# Flight_Controller.net
KiCad netlist of a schematic drawn in Altium Designer
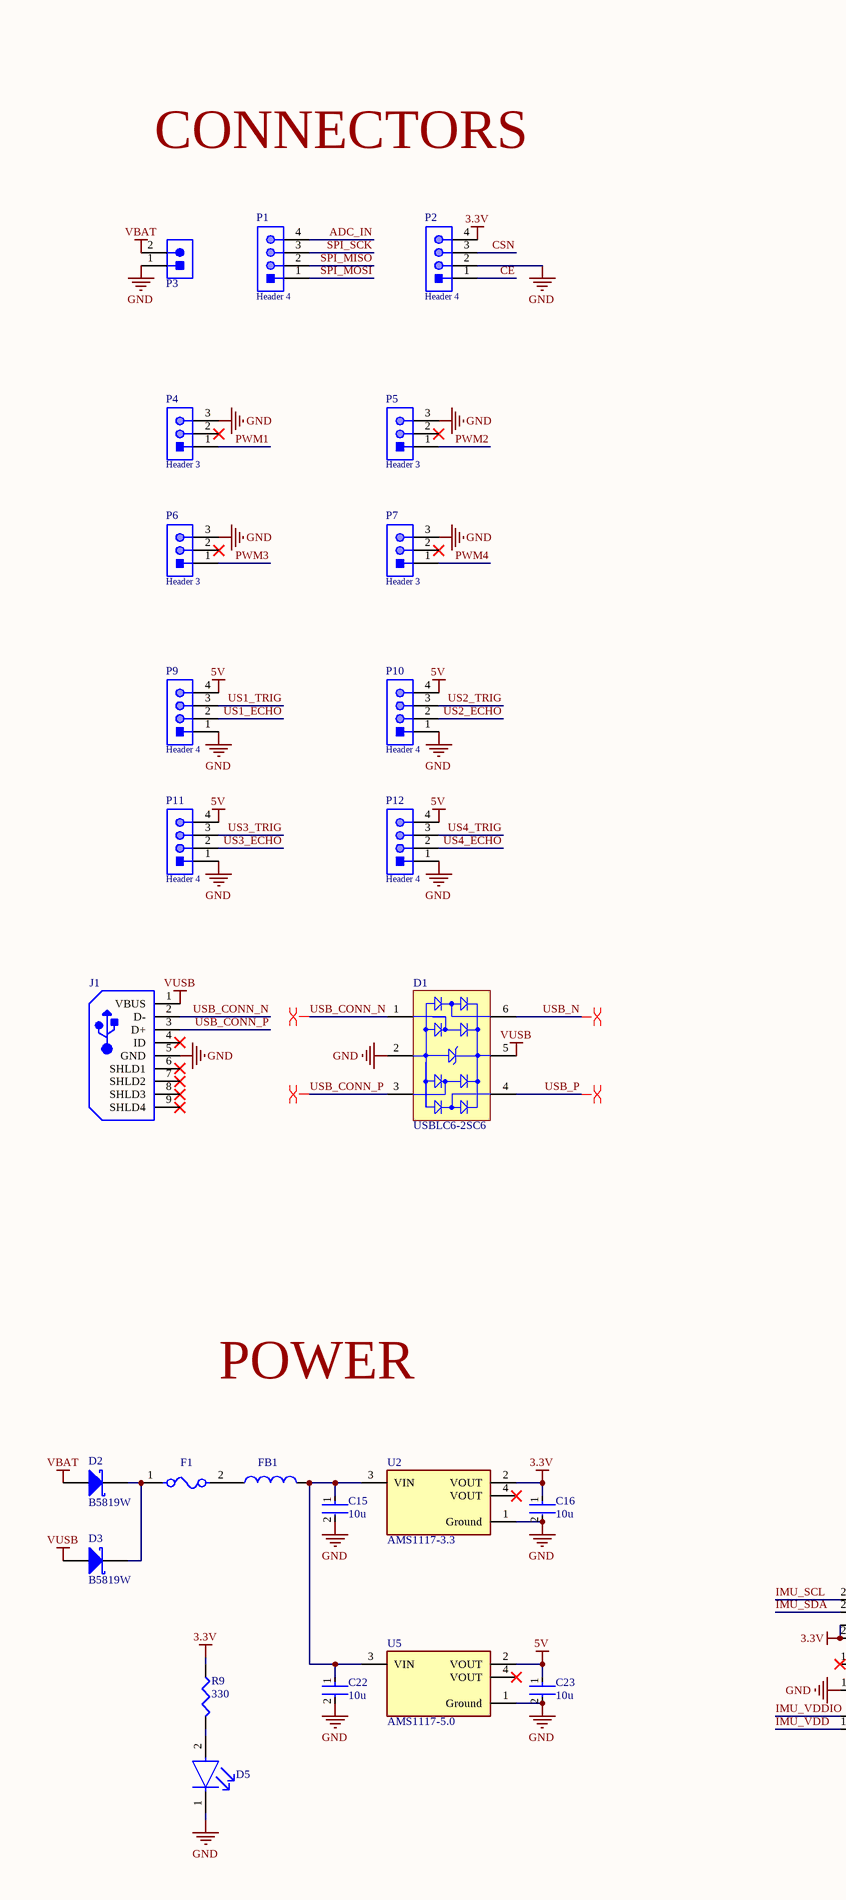
[diagram p0: Flight Controller.SchDoc, left]
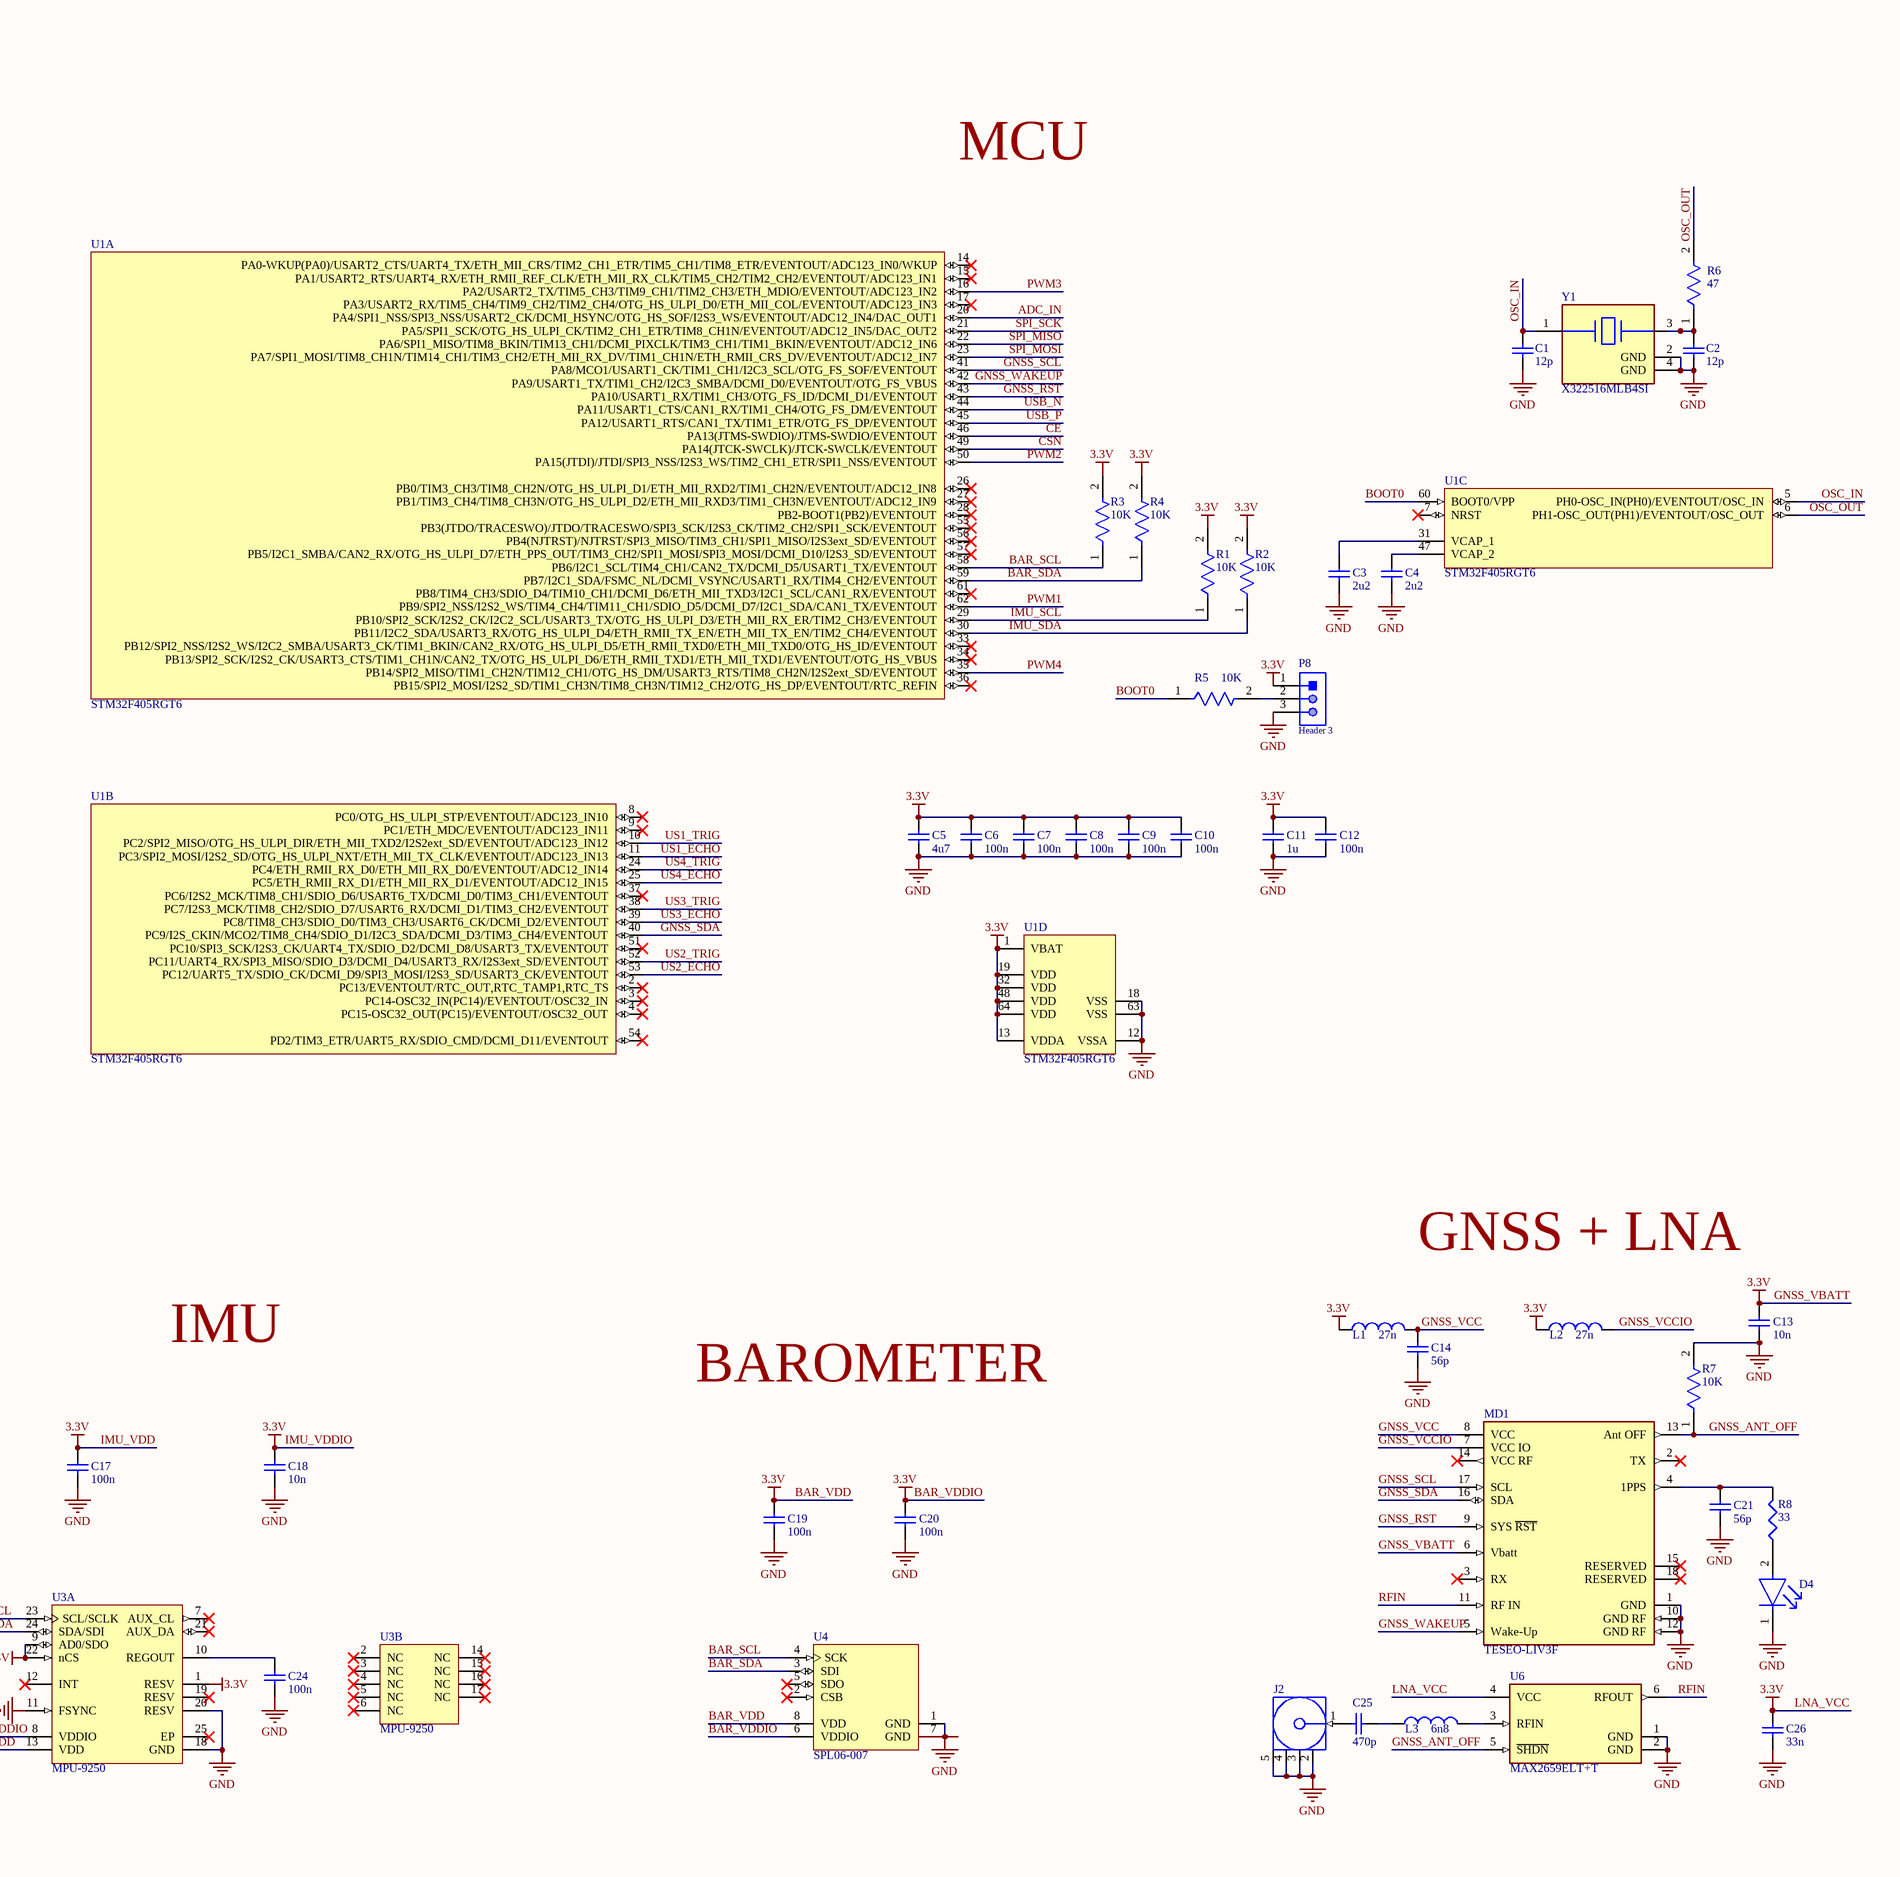
[diagram p1: Flight Controller.SchDoc, right]

(export (version "E")
  (design (tool "Eeschema 10.0.6"))
  (components
    (comp (ref "C1")
      (value "12p")
      (footprint "0402")
      (description "Capacitor (Semiconductor SIM Model)")
      (fields (field (name "Comment") "Cap Semi") (field (name "PUBLISHER") "Altium Limited"))
      (libsource (lib "Miscellaneous Devices") (part "Cap Semi"))
    )
    (comp (ref "C2")
      (value "12p")
      (footprint "0402")
      (description "Capacitor (Semiconductor SIM Model)")
      (fields (field (name "Comment") "Cap Semi") (field (name "PUBLISHER") "Altium Limited"))
      (libsource (lib "Miscellaneous Devices") (part "Cap Semi"))
    )
    (comp (ref "C3")
      (value "2u2")
      (footprint "1608[0603]")
      (description "Capacitor (Semiconductor SIM Model)")
      (fields (field (name "Comment") "Cap Semi") (field (name "PUBLISHER") "Altium Limited"))
      (libsource (lib "Miscellaneous Devices") (part "Cap Semi"))
    )
    (comp (ref "C4")
      (value "2u2")
      (footprint "1608[0603]")
      (description "Capacitor (Semiconductor SIM Model)")
      (fields (field (name "Comment") "Cap Semi") (field (name "PUBLISHER") "Altium Limited"))
      (libsource (lib "Miscellaneous Devices") (part "Cap Semi"))
    )
    (comp (ref "C5")
      (value "4u7")
      (footprint "1608[0603]")
      (description "Capacitor (Semiconductor SIM Model)")
      (fields (field (name "Comment") "Cap Semi") (field (name "PUBLISHER") "Altium Limited"))
      (libsource (lib "Miscellaneous Devices") (part "Cap Semi"))
    )
    (comp (ref "C6")
      (value "100n")
      (footprint "0402")
      (description "Capacitor (Semiconductor SIM Model)")
      (fields (field (name "Comment") "Cap Semi") (field (name "PUBLISHER") "Altium Limited"))
      (libsource (lib "Miscellaneous Devices") (part "Cap Semi"))
    )
    (comp (ref "C7")
      (value "100n")
      (footprint "0402")
      (description "Capacitor (Semiconductor SIM Model)")
      (fields (field (name "Comment") "Cap Semi") (field (name "PUBLISHER") "Altium Limited"))
      (libsource (lib "Miscellaneous Devices") (part "Cap Semi"))
    )
    (comp (ref "C8")
      (value "100n")
      (footprint "0402")
      (description "Capacitor (Semiconductor SIM Model)")
      (fields (field (name "Comment") "Cap Semi") (field (name "PUBLISHER") "Altium Limited"))
      (libsource (lib "Miscellaneous Devices") (part "Cap Semi"))
    )
    (comp (ref "C9")
      (value "100n")
      (footprint "0402")
      (description "Capacitor (Semiconductor SIM Model)")
      (fields (field (name "Comment") "Cap Semi") (field (name "PUBLISHER") "Altium Limited"))
      (libsource (lib "Miscellaneous Devices") (part "Cap Semi"))
    )
    (comp (ref "C10")
      (value "100n")
      (footprint "0402")
      (description "Capacitor (Semiconductor SIM Model)")
      (fields (field (name "Comment") "Cap Semi") (field (name "PUBLISHER") "Altium Limited"))
      (libsource (lib "Miscellaneous Devices") (part "Cap Semi"))
    )
    (comp (ref "C11")
      (value "1u")
      (footprint "1608[0603]")
      (description "Capacitor (Semiconductor SIM Model)")
      (fields (field (name "Comment") "Cap Semi") (field (name "PUBLISHER") "Altium Limited"))
      (libsource (lib "Miscellaneous Devices") (part "Cap Semi"))
    )
    (comp (ref "C12")
      (value "100n")
      (footprint "0402")
      (description "Capacitor (Semiconductor SIM Model)")
      (fields (field (name "Comment") "Cap Semi") (field (name "PUBLISHER") "Altium Limited"))
      (libsource (lib "Miscellaneous Devices") (part "Cap Semi"))
    )
    (comp (ref "C13")
      (value "10n")
      (footprint "0402")
      (description "Capacitor (Semiconductor SIM Model)")
      (fields (field (name "Comment") "Cap Semi") (field (name "PUBLISHER") "Altium Limited"))
      (libsource (lib "Miscellaneous Devices") (part "Cap Semi"))
    )
    (comp (ref "C14")
      (value "56p")
      (footprint "0402")
      (description "Capacitor (Semiconductor SIM Model)")
      (fields (field (name "Comment") "Cap Semi") (field (name "PUBLISHER") "Altium Limited"))
      (libsource (lib "Miscellaneous Devices") (part "Cap Semi"))
    )
    (comp (ref "C15")
      (value "10u")
      (footprint "FP-CL21-IPC_B")
      (description "CL21 Series 0805 10uF 25V ±10% Tolerance X5R Multilayer Ceramic Chip Capacitor")
      (fields (field (name "TOLERANCE") "10%"))
      (libsource (lib "Altium Content Vault") (part "b4654b650e69147ec39a6b967a45e02"))
    )
    (comp (ref "C16")
      (value "10u")
      (footprint "FP-CL21-IPC_B")
      (description "CL21 Series 0805 10uF 25V ±10% Tolerance X5R Multilayer Ceramic Chip Capacitor")
      (fields (field (name "TOLERANCE") "10%"))
      (libsource (lib "Altium Content Vault") (part "b4654b650e69147ec39a6b967a45e02"))
    )
    (comp (ref "C17")
      (value "100n")
      (footprint "0402")
      (description "Capacitor (Semiconductor SIM Model)")
      (fields (field (name "Comment") "Cap Semi") (field (name "PUBLISHER") "Altium Limited"))
      (libsource (lib "Miscellaneous Devices") (part "Cap Semi"))
    )
    (comp (ref "C18")
      (value "10n")
      (footprint "0402")
      (description "Capacitor (Semiconductor SIM Model)")
      (fields (field (name "Comment") "Cap Semi") (field (name "PUBLISHER") "Altium Limited"))
      (libsource (lib "Miscellaneous Devices") (part "Cap Semi"))
    )
    (comp (ref "C19")
      (value "100n")
      (footprint "0402")
      (description "Capacitor (Semiconductor SIM Model)")
      (fields (field (name "Comment") "Cap Semi") (field (name "PUBLISHER") "Altium Limited"))
      (libsource (lib "Miscellaneous Devices") (part "Cap Semi"))
    )
    (comp (ref "C20")
      (value "100n")
      (footprint "0402")
      (description "Capacitor (Semiconductor SIM Model)")
      (fields (field (name "Comment") "Cap Semi") (field (name "PUBLISHER") "Altium Limited"))
      (libsource (lib "Miscellaneous Devices") (part "Cap Semi"))
    )
    (comp (ref "C21")
      (value "56p")
      (footprint "0402")
      (description "Capacitor (Semiconductor SIM Model)")
      (fields (field (name "Comment") "Cap Semi") (field (name "PUBLISHER") "Altium Limited"))
      (libsource (lib "Miscellaneous Devices") (part "Cap Semi"))
    )
    (comp (ref "C22")
      (value "10u")
      (footprint "FP-CL21-IPC_B")
      (description "CL21 Series 0805 10uF 25V ±10% Tolerance X5R Multilayer Ceramic Chip Capacitor")
      (fields (field (name "TOLERANCE") "10%"))
      (libsource (lib "Altium Content Vault") (part "b4654b650e69147ec39a6b967a45e02"))
    )
    (comp (ref "C23")
      (value "10u")
      (footprint "FP-CL21-IPC_B")
      (description "CL21 Series 0805 10uF 25V ±10% Tolerance X5R Multilayer Ceramic Chip Capacitor")
      (fields (field (name "TOLERANCE") "10%"))
      (libsource (lib "Altium Content Vault") (part "b4654b650e69147ec39a6b967a45e02"))
    )
    (comp (ref "C24")
      (value "100n")
      (footprint "0402")
      (description "Capacitor (Semiconductor SIM Model)")
      (fields (field (name "Comment") "Cap Semi") (field (name "PUBLISHER") "Altium Limited"))
      (libsource (lib "Miscellaneous Devices") (part "Cap Semi"))
    )
    (comp (ref "C25")
      (value "470p")
      (footprint "0402")
      (description "Capacitor (Semiconductor SIM Model)")
      (fields (field (name "Comment") "Cap Semi") (field (name "PUBLISHER") "Altium Limited"))
      (libsource (lib "Miscellaneous Devices") (part "Cap Semi"))
    )
    (comp (ref "C26")
      (value "33n")
      (footprint "0402")
      (description "Capacitor (Semiconductor SIM Model)")
      (fields (field (name "Comment") "Cap Semi") (field (name "PUBLISHER") "Altium Limited"))
      (libsource (lib "Miscellaneous Devices") (part "Cap Semi"))
    )
    (comp (ref "D1")
      (value "USBLC6-2SC6")
      (footprint "STM-SOT23-6L_V")
      (description "Very low capacitance ESD protection, 3.5 pF, -40 to 125 degC, 6-Pin SOT23, RoHS, Tape and Reel")
      (fields (field (name "MANUFACTURER") "STMicroelectronics"))
      (libsource (lib "Altium Content Vault") (part "STM-USB_DVI_HDMIULC6-4SC6X-SOT23-6L"))
    )
    (comp (ref "D2")
      (value "B5819W")
      (footprint "MCC-SOD123_V")
      (description "Schottky Barrier Rectifier, 1 A, 40 Vrm, -65 to 125 degC, 2-Pin SOD123, RoHS, Tape and Reel")
      (fields (field (name "MANUFACTURER") "Micro Commercial Components"))
      (libsource (lib "Altium Content Vault") (part "DSKY-AK-2"))
    )
    (comp (ref "D3")
      (value "B5819W")
      (footprint "MCC-SOD123_V")
      (description "Schottky Barrier Rectifier, 1 A, 40 Vrm, -65 to 125 degC, 2-Pin SOD123, RoHS, Tape and Reel")
      (fields (field (name "MANUFACTURER") "Micro Commercial Components"))
      (libsource (lib "Altium Content Vault") (part "DSKY-AK-2"))
    )
    (comp (ref "D4")
      (value "597-3901-831F")
      (footprint "FP-597-MFG")
      (description "LED COOL WHITE 2SMD")
      (fields
        (field (name "OCTOPART") "https://octopart.com/597-3901-831f-dialight-10598902")
        (field (name "MANUFACTURER") "Dialight")
      )
      (libsource (lib "Altium Content Vault") (part "8706943c75ba83719d021d2fdc84c58"))
    )
    (comp (ref "D5")
      (value "597-3901-831F")
      (footprint "FP-597-MFG")
      (description "LED COOL WHITE 2SMD")
      (fields
        (field (name "OCTOPART") "https://octopart.com/597-3901-831f-dialight-10598902")
        (field (name "MANUFACTURER") "Dialight")
      )
      (libsource (lib "Altium Content Vault") (part "8706943c75ba83719d021d2fdc84c58"))
    )
    (comp (ref "F1")
      (value "nSMD050-24V")
      (footprint "FP-0466-MFG")
      (description "FUSE BOARD MNT 1A 63VAC/VDC 1206")
      (fields
        (field (name "MANUFACTURER PART NUMBER") "0466001.NR")
        (field (name "MANUFACTURER") "Littelfuse Inc")
      )
      (libsource (lib "Altium Content Vault") (part "5bcf9b9f640e542cf0359d10258e979"))
    )
    (comp (ref "FB1")
      (value "GZ2012D601TF")
      (footprint "SNLD-CHIP2-2012X105_V")
      (fields (field (name "MANUFACTURER") "Sunlord"))
      (libsource (lib "Altium Content Vault") (part "SNLD-FB-2"))
    )
    (comp (ref "J1")
      (value "65100516121")
      (footprint "WE-65100516121_V")
      (description "MINI USB 2.0 SMT Type B 5 Contacts, 30 V, -40 to 105 degC, RoHS, Tape and Reel")
      (fields (field (name "MANUFACTURER") "Wuerth Elektronik"))
      (libsource (lib "Altium Content Vault") (part "USB-5-4SHLD"))
    )
    (comp (ref "J2")
      (value "CONSMA001")
      (footprint "CON-SMA")
      (description "Female PCB Mount Connector, Thru-Hole")
      (libsource (lib "Altium Content Vault") (part "CN-1P-F-RF5"))
    )
    (comp (ref "L1")
      (value "27n")
      (footprint "0402-A")
      (description "Inductor")
      (fields (field (name "PUBLISHER") "Altium Limited"))
      (libsource (lib "Miscellaneous Devices") (part "Inductor"))
    )
    (comp (ref "L2")
      (value "27n")
      (footprint "0402-A")
      (description "Inductor")
      (fields (field (name "PUBLISHER") "Altium Limited"))
      (libsource (lib "Miscellaneous Devices") (part "Inductor"))
    )
    (comp (ref "L3")
      (value "6n8")
      (footprint "0402-A")
      (description "Inductor")
      (fields (field (name "PUBLISHER") "Altium Limited"))
      (libsource (lib "Miscellaneous Devices") (part "Inductor"))
    )
    (comp (ref "MD1")
      (value "TESEO-LIV3F")
      (footprint "FP-LCC-18-MFG")
      (description "RF RCVR GNSS/GPS 1.575GHZ 18LCC")
      (fields
        (field (name "MANUFACTURER") "STMicroelectronics")
        (field (name "OCTOPART") "https://octopart.com/teseo-liv3f-stmicroelectronics-84762432")
      )
      (libsource (lib "Altium Content Vault") (part "a9d99e4f4ab5d9a165d150092334cf6"))
    )
    (comp (ref "P1")
      (value "Header 4")
      (footprint "61300411121")
      (description "THT Vertical Pin Header WR-PHD, Pitch 2.54 mm, Single Row, 4 pins")
      (fields
        (field (name "MANUFACTURER") "Wurth Elektronik")
        (field (name "PART NUMBER") "61300411121")
        (field (name "PUBLISHER") "WurthElektronik")
      )
      (libsource (lib "Altium Content Vault") (part "WE-CN-1P-M-R4"))
    )
    (comp (ref "P2")
      (value "Header 4")
      (footprint "61300411121")
      (description "THT Vertical Pin Header WR-PHD, Pitch 2.54 mm, Single Row, 4 pins")
      (fields
        (field (name "MANUFACTURER") "Wurth Elektronik")
        (field (name "PART NUMBER") "61300411121")
        (field (name "PUBLISHER") "WurthElektronik")
      )
      (libsource (lib "Altium Content Vault") (part "WE-CN-1P-M-R4"))
    )
    (comp (ref "P3")
      (value "SCREW-5.0/5.08 2WAYS")
      (footprint "SCREW-5.0-2WAYS_V")
      (description "Socket, Screw Terminal Block, 2 Way, 5.0 mm Pitch, 90 Degree Angle, Through-Hole")
      (fields (field (name "MANUFACTURER") "No Vendor"))
      (libsource (lib "Altium Content Vault") (part "SCREW-2WAYS"))
    )
    (comp (ref "P4")
      (value "Header 3")
      (footprint "61300311121")
      (description "THT Vertical Pin Header WR-PHD, Pitch 2.54 mm, Single Row, 3 pins")
      (fields
        (field (name "PART NUMBER") "61300311121")
        (field (name "MANUFACTURER") "Wurth Elektronik")
        (field (name "PUBLISHER") "WurthElektronik")
      )
      (libsource (lib "Altium Content Vault") (part "WE-CN-1P-M-R3"))
    )
    (comp (ref "P5")
      (value "Header 3")
      (footprint "61300311121")
      (description "THT Vertical Pin Header WR-PHD, Pitch 2.54 mm, Single Row, 3 pins")
      (fields
        (field (name "PART NUMBER") "61300311121")
        (field (name "MANUFACTURER") "Wurth Elektronik")
        (field (name "PUBLISHER") "WurthElektronik")
      )
      (libsource (lib "Altium Content Vault") (part "WE-CN-1P-M-R3"))
    )
    (comp (ref "P6")
      (value "Header 3")
      (footprint "61300311121")
      (description "THT Vertical Pin Header WR-PHD, Pitch 2.54 mm, Single Row, 3 pins")
      (fields
        (field (name "PART NUMBER") "61300311121")
        (field (name "MANUFACTURER") "Wurth Elektronik")
        (field (name "PUBLISHER") "WurthElektronik")
      )
      (libsource (lib "Altium Content Vault") (part "WE-CN-1P-M-R3"))
    )
    (comp (ref "P7")
      (value "Header 3")
      (footprint "61300311121")
      (description "THT Vertical Pin Header WR-PHD, Pitch 2.54 mm, Single Row, 3 pins")
      (fields
        (field (name "PART NUMBER") "61300311121")
        (field (name "MANUFACTURER") "Wurth Elektronik")
        (field (name "PUBLISHER") "WurthElektronik")
      )
      (libsource (lib "Altium Content Vault") (part "WE-CN-1P-M-R3"))
    )
    (comp (ref "P8")
      (value "Header 3")
      (footprint "61300311121")
      (description "THT Vertical Pin Header WR-PHD, Pitch 2.54 mm, Single Row, 3 pins")
      (fields
        (field (name "PART NUMBER") "61300311121")
        (field (name "MANUFACTURER") "Wurth Elektronik")
        (field (name "PUBLISHER") "WurthElektronik")
      )
      (libsource (lib "") (part "WE-CN-1P-M-R3_1"))
    )
    (comp (ref "P9")
      (value "Header 4")
      (footprint "61300411121")
      (description "THT Vertical Pin Header WR-PHD, Pitch 2.54 mm, Single Row, 4 pins")
      (fields
        (field (name "MANUFACTURER") "Wurth Elektronik")
        (field (name "PART NUMBER") "61300411121")
        (field (name "PUBLISHER") "WurthElektronik")
      )
      (libsource (lib "Altium Content Vault") (part "WE-CN-1P-M-R4"))
    )
    (comp (ref "P10")
      (value "Header 4")
      (footprint "61300411121")
      (description "THT Vertical Pin Header WR-PHD, Pitch 2.54 mm, Single Row, 4 pins")
      (fields
        (field (name "MANUFACTURER") "Wurth Elektronik")
        (field (name "PART NUMBER") "61300411121")
        (field (name "PUBLISHER") "WurthElektronik")
      )
      (libsource (lib "Altium Content Vault") (part "WE-CN-1P-M-R4"))
    )
    (comp (ref "P11")
      (value "Header 4")
      (footprint "61300411121")
      (description "THT Vertical Pin Header WR-PHD, Pitch 2.54 mm, Single Row, 4 pins")
      (fields
        (field (name "MANUFACTURER") "Wurth Elektronik")
        (field (name "PART NUMBER") "61300411121")
        (field (name "PUBLISHER") "WurthElektronik")
      )
      (libsource (lib "Altium Content Vault") (part "WE-CN-1P-M-R4"))
    )
    (comp (ref "P12")
      (value "Header 4")
      (footprint "61300411121")
      (description "THT Vertical Pin Header WR-PHD, Pitch 2.54 mm, Single Row, 4 pins")
      (fields
        (field (name "MANUFACTURER") "Wurth Elektronik")
        (field (name "PART NUMBER") "61300411121")
        (field (name "PUBLISHER") "WurthElektronik")
      )
      (libsource (lib "Altium Content Vault") (part "WE-CN-1P-M-R4"))
    )
    (comp (ref "R1")
      (value "10K")
      (footprint "FP-CRCW0402-e3-MFG")
      (description "RES SMD 10K OHM 1% 1/16W 0402")
      (fields (field (name "TOLERANCE") "1%"))
      (libsource (lib "Altium Content Vault") (part "1029c3af85768c4190bb7ad29bc67b5"))
    )
    (comp (ref "R2")
      (value "10K")
      (footprint "FP-CRCW0402-e3-MFG")
      (description "RES SMD 10K OHM 1% 1/16W 0402")
      (fields (field (name "TOLERANCE") "1%"))
      (libsource (lib "Altium Content Vault") (part "1029c3af85768c4190bb7ad29bc67b5"))
    )
    (comp (ref "R3")
      (value "10K")
      (footprint "FP-CRCW0402-e3-MFG")
      (description "RES SMD 10K OHM 1% 1/16W 0402")
      (fields (field (name "TOLERANCE") "1%"))
      (libsource (lib "Altium Content Vault") (part "1029c3af85768c4190bb7ad29bc67b5"))
    )
    (comp (ref "R4")
      (value "10K")
      (footprint "FP-CRCW0402-e3-MFG")
      (description "RES SMD 10K OHM 1% 1/16W 0402")
      (fields (field (name "TOLERANCE") "1%"))
      (libsource (lib "Altium Content Vault") (part "1029c3af85768c4190bb7ad29bc67b5"))
    )
    (comp (ref "R5")
      (value "10K")
      (footprint "FP-CRCW0402-e3-MFG")
      (description "RES SMD 10K OHM 1% 1/16W 0402")
      (fields (field (name "TOLERANCE") "1%"))
      (libsource (lib "Altium Content Vault") (part "1029c3af85768c4190bb7ad29bc67b5"))
    )
    (comp (ref "R6")
      (value "47")
      (footprint "FP-CRCW0402-e3-MFG")
      (description "RES SMD 10K OHM 1% 1/16W 0402")
      (fields (field (name "TOLERANCE") "1%"))
      (libsource (lib "Altium Content Vault") (part "1029c3af85768c4190bb7ad29bc67b5"))
    )
    (comp (ref "R7")
      (value "10K")
      (footprint "FP-CRCW0402-e3-MFG")
      (description "RES SMD 10K OHM 1% 1/16W 0402")
      (fields (field (name "TOLERANCE") "1%"))
      (libsource (lib "Altium Content Vault") (part "1029c3af85768c4190bb7ad29bc67b5"))
    )
    (comp (ref "R8")
      (value "33")
      (footprint "J1-0603")
      (description "Resistor")
      (fields (field (name "Comment") "Res3") (field (name "PUBLISHER") "Altium Limited"))
      (libsource (lib "Miscellaneous Devices") (part "Res3"))
    )
    (comp (ref "R9")
      (value "330")
      (footprint "J1-0603")
      (description "Resistor")
      (fields (field (name "Comment") "Res3") (field (name "PUBLISHER") "Altium Limited"))
      (libsource (lib "Miscellaneous Devices") (part "Res3"))
    )
    (comp (ref "U1")
      (value "STM32F405RGT6")
      (footprint "STM-LQFP64_N")
      (fields (field (name "MANUFACTURER") "STMicroelectronics"))
      (libsource (lib "Altium Content Vault") (part "MC-ARM-STM32F4X5-SQ64"))
    )
    (comp (ref "U2")
      (value "AMS1117-3.3")
      (footprint "FP-AMS1117-IPC_C")
      (description "LDO Voltage Regulators 1A, 3.3V")
      (fields
        (field (name "OCTOPART") "https://octopart.com/ams1117-3.3-advanced+monolithic+systems-25899300")
        (field (name "MANUFACTURER") "Advanced Monolithic Systems")
      )
      (libsource (lib "Altium Content Vault") (part "8bdbb5f8e77002000e30dd2845d0354"))
    )
    (comp (ref "U3")
      (value "MPU-9250")
      (footprint "INSE-QFN-24-1700X1540TP_M")
      (description "9-axis MotionTracking device, 2.4 to 3,6 V, -40 to 85 degC, 24-Pin QFN, RoHS, Tape and Reel")
      (fields (field (name "MANUFACTURER") "InvenSense"))
      (libsource (lib "Altium Content Vault") (part "INSE-MPU-9250-QFN-24"))
    )
    (comp (ref "U4")
      (value "SPL06-007")
      (footprint "BOSC-LGA-8_V")
      (description "Digital Pressure Sensor, 1.71 to 3.6 V, -40 to 85 degC, 8-Pin LGA, RoHS, Tape and Reel")
      (fields (field (name "MANUFACTURER") "Bosch Sensortec"))
      (libsource (lib "Altium Content Vault") (part "BOSC-BMP280-LGA-8"))
    )
    (comp (ref "U5")
      (value "AMS1117-5.0")
      (footprint "FP-AMS1117-IPC_C")
      (description "LDO Voltage Regulators 1A, 5V")
      (fields
        (field (name "MANUFACTURER PART NUMBER") "AMS1117-3.3")
        (field (name "OCTOPART") "https://octopart.com/ams1117-3.3-advanced+monolithic+systems-25899300")
      )
      (libsource (lib "Altium Content Vault") (part "8bdbb5f8e77002000e30dd2845d0354"))
    )
    (comp (ref "U6")
      (value "MAX2659ELT+T")
      (footprint "FP-L611-2-MFG")
      (description "GPS Amp Single Low Noise 1.75GHz 3.6V 6-Pin UDFN")
      (libsource (lib "Altium Content Vault") (part "fca23d189b6920f08195121cb41012b"))
    )
    (comp (ref "Y1")
      (value "X322516MLB4SI")
      (footprint "FP-XRCJK-MFG")
      (description "Crystal Unit SMD 3225 Seam Sealing 20MHz 10ppm")
      (libsource (lib "Altium Content Vault") (part "99ec9465e150dc3113a28528ba6143b"))
    )
  )
  (nets
    (net (code "1") (name "/ADC_IN") (class "Default")
      (node (ref "P1") (pin "4") (pinfunction "4_4") (pintype "passive"))
      (node (ref "U1") (pin "20") (pinfunction "PA4/SPI1_NSS/SPI3_NSS/USART2_CK/DCMI_HSYNC/OTG_HS_SOF/I2S3_WS/EVENTOUT/ADC12_IN4/DAC_OUT1_20") (pintype "bidirectional"))
    )
    (net (code "2") (name "/BAR_SCL") (class "Default")
      (node (ref "R3") (pin "1") (pinfunction "1_1") (pintype "passive"))
      (node (ref "U1") (pin "58") (pinfunction "PB6/I2C1_SCL/TIM4_CH1/CAN2_TX/DCMI_D5/USART1_TX/EVENTOUT_58") (pintype "bidirectional"))
      (node (ref "U4") (pin "4") (pinfunction "SCK_4") (pintype "input"))
    )
    (net (code "3") (name "/BAR_SDA") (class "Default")
      (node (ref "R4") (pin "1") (pinfunction "1_1") (pintype "passive"))
      (node (ref "U1") (pin "59") (pinfunction "PB7/I2C1_SDA/FSMC_NL/DCMI_VSYNC/USART1_RX/TIM4_CH2/EVENTOUT_59") (pintype "bidirectional"))
      (node (ref "U4") (pin "3") (pinfunction "SDI_3") (pintype "bidirectional"))
    )
    (net (code "4") (name "/BOOT0") (class "Default")
      (node (ref "R5") (pin "1") (pinfunction "1_1") (pintype "passive"))
      (node (ref "U1") (pin "60") (pinfunction "BOOT0/VPP_60") (pintype "input"))
    )
    (net (code "5") (name "/CE") (class "Default")
      (node (ref "P2") (pin "1") (pinfunction "1_1") (pintype "passive"))
      (node (ref "U1") (pin "46") (pinfunction "PA13(JTMS-SWDIO)/JTMS-SWDIO/EVENTOUT_46") (pintype "bidirectional"))
    )
    (net (code "6") (name "/CSN") (class "Default")
      (node (ref "P2") (pin "3") (pinfunction "3_3") (pintype "passive"))
      (node (ref "U1") (pin "49") (pinfunction "PA14(JTCK-SWCLK)/JTCK-SWCLK/EVENTOUT_49") (pintype "bidirectional"))
    )
    (net (code "7") (name "/GNSS_ANT_OFF") (class "Default")
      (node (ref "MD1") (pin "13") (pinfunction "Ant_OFF_13") (pintype "output"))
      (node (ref "R7") (pin "1") (pinfunction "1_1") (pintype "passive"))
      (node (ref "U6") (pin "5") (pinfunction "~{SHDN}_5") (pintype "input"))
    )
    (net (code "8") (name "/GNSS_RST") (class "Default")
      (node (ref "MD1") (pin "9") (pinfunction "SYS_~{RST}_9") (pintype "input"))
      (node (ref "U1") (pin "43") (pinfunction "PA10/USART1_RX/TIM1_CH3/OTG_FS_ID/DCMI_D1/EVENTOUT_43") (pintype "bidirectional"))
    )
    (net (code "9") (name "/GNSS_SCL") (class "Default")
      (node (ref "MD1") (pin "17") (pinfunction "SCL_17") (pintype "input"))
      (node (ref "U1") (pin "41") (pinfunction "PA8/MCO1/USART1_CK/TIM1_CH1/I2C3_SCL/OTG_FS_SOF/EVENTOUT_41") (pintype "bidirectional"))
    )
    (net (code "10") (name "/GNSS_SDA") (class "Default")
      (node (ref "MD1") (pin "16") (pinfunction "SDA_16") (pintype "bidirectional"))
      (node (ref "U1") (pin "40") (pinfunction "PC9/I2S_CKIN/MCO2/TIM8_CH4/SDIO_D1/I2C3_SDA/DCMI_D3/TIM3_CH4/EVENTOUT_40") (pintype "bidirectional"))
    )
    (net (code "11") (name "/GNSS_VCC") (class "Default")
      (node (ref "C14") (pin "2") (pinfunction "2_2") (pintype "passive"))
      (node (ref "L1") (pin "2") (pinfunction "2_2") (pintype "passive"))
      (node (ref "MD1") (pin "8") (pinfunction "VCC_8") (pintype "power_in"))
    )
    (net (code "12") (name "/GNSS_VCCIO") (class "Default")
      (node (ref "L2") (pin "2") (pinfunction "2_2") (pintype "passive"))
      (node (ref "MD1") (pin "7") (pinfunction "VCC_IO_7") (pintype "power_in"))
    )
    (net (code "13") (name "/GNSS_WAKEUP") (class "Default")
      (node (ref "MD1") (pin "5") (pinfunction "Wake-Up_5") (pintype "input"))
      (node (ref "U1") (pin "42") (pinfunction "PA9/USART1_TX/TIM1_CH2/I2C3_SMBA/DCMI_D0/EVENTOUT/OTG_FS_VBUS_42") (pintype "bidirectional"))
    )
    (net (code "14") (name "/IMU_SCL") (class "Default")
      (node (ref "R1") (pin "1") (pinfunction "1_1") (pintype "passive"))
      (node (ref "U1") (pin "29") (pinfunction "PB10/SPI2_SCK/I2S2_CK/I2C2_SCL/USART3_TX/OTG_HS_ULPI_D3/ETH_MII_RX_ER/TIM2_CH3/EVENTOUT_29") (pintype "bidirectional"))
      (node (ref "U3") (pin "23") (pinfunction "SCL/SCLK_23") (pintype "input"))
    )
    (net (code "15") (name "/IMU_SDA") (class "Default")
      (node (ref "R2") (pin "1") (pinfunction "1_1") (pintype "passive"))
      (node (ref "U1") (pin "30") (pinfunction "PB11/I2C2_SDA/USART3_RX/OTG_HS_ULPI_D4/ETH_RMII_TX_EN/ETH_MII_TX_EN/TIM2_CH4/EVENTOUT_30") (pintype "bidirectional"))
      (node (ref "U3") (pin "24") (pinfunction "SDA/SDI_24") (pintype "bidirectional"))
    )
    (net (code "16") (name "/OSC_IN") (class "Default")
      (node (ref "C1") (pin "1") (pinfunction "1_1") (pintype "passive"))
      (node (ref "U1") (pin "5") (pinfunction "PH0-OSC_IN(PH0)/EVENTOUT/OSC_IN_5") (pintype "bidirectional"))
      (node (ref "Y1") (pin "1") (pinfunction "1_1") (pintype "passive"))
    )
    (net (code "17") (name "/OSC_OUT") (class "Default")
      (node (ref "R6") (pin "2") (pinfunction "2_2") (pintype "passive"))
      (node (ref "U1") (pin "6") (pinfunction "PH1-OSC_OUT(PH1)/EVENTOUT/OSC_OUT_6") (pintype "bidirectional"))
    )
    (net (code "18") (name "/PWM1") (class "Default")
      (node (ref "P4") (pin "1") (pinfunction "1_1") (pintype "passive"))
      (node (ref "U1") (pin "62") (pinfunction "PB9/SPI2_NSS/I2S2_WS/TIM4_CH4/TIM11_CH1/SDIO_D5/DCMI_D7/I2C1_SDA/CAN1_TX/EVENTOUT_62") (pintype "bidirectional"))
    )
    (net (code "19") (name "/PWM2") (class "Default")
      (node (ref "P5") (pin "1") (pinfunction "1_1") (pintype "passive"))
      (node (ref "U1") (pin "50") (pinfunction "PA15(JTDI)/JTDI/SPI3_NSS/I2S3_WS/TIM2_CH1_ETR/SPI1_NSS/EVENTOUT_50") (pintype "bidirectional"))
    )
    (net (code "20") (name "/PWM3") (class "Default")
      (node (ref "P6") (pin "1") (pinfunction "1_1") (pintype "passive"))
      (node (ref "U1") (pin "16") (pinfunction "PA2/USART2_TX/TIM5_CH3/TIM9_CH1/TIM2_CH3/ETH_MDIO/EVENTOUT/ADC123_IN2_16") (pintype "bidirectional"))
    )
    (net (code "21") (name "/PWM4") (class "Default")
      (node (ref "P7") (pin "1") (pinfunction "1_1") (pintype "passive"))
      (node (ref "U1") (pin "35") (pinfunction "PB14/SPI2_MISO/TIM1_CH2N/TIM12_CH1/OTG_HS_DM/USART3_RTS/TIM8_CH2N/I2S2ext_SD/EVENTOUT_35") (pintype "bidirectional"))
    )
    (net (code "22") (name "/RFIN") (class "Default")
      (node (ref "MD1") (pin "11") (pinfunction "RF_IN_11") (pintype "input"))
      (node (ref "U6") (pin "6") (pinfunction "RFOUT_6") (pintype "output"))
    )
    (net (code "23") (name "/SPI_MISO") (class "Default")
      (node (ref "P1") (pin "2") (pinfunction "2_2") (pintype "passive"))
      (node (ref "U1") (pin "22") (pinfunction "PA6/SPI1_MISO/TIM8_BKIN/TIM13_CH1/DCMI_PIXCLK/TIM3_CH1/TIM1_BKIN/EVENTOUT/ADC12_IN6_22") (pintype "bidirectional"))
    )
    (net (code "24") (name "/SPI_MOSI") (class "Default")
      (node (ref "P1") (pin "1") (pinfunction "1_1") (pintype "passive"))
      (node (ref "U1") (pin "23") (pinfunction "PA7/SPI1_MOSI/TIM8_CH1N/TIM14_CH1/TIM3_CH2/ETH_MII_RX_DV/TIM1_CH1N/ETH_RMII_CRS_DV/EVENTOUT/ADC12_IN7_23") (pintype "bidirectional"))
    )
    (net (code "25") (name "/SPI_SCK") (class "Default")
      (node (ref "P1") (pin "3") (pinfunction "3_3") (pintype "passive"))
      (node (ref "U1") (pin "21") (pinfunction "PA5/SPI1_SCK/OTG_HS_ULPI_CK/TIM2_CH1_ETR/TIM8_CH1N/EVENTOUT/ADC12_IN5/DAC_OUT2_21") (pintype "bidirectional"))
    )
    (net (code "26") (name "/US1_ECHO") (class "Default")
      (node (ref "P9") (pin "2") (pinfunction "2_2") (pintype "passive"))
      (node (ref "U1") (pin "11") (pinfunction "PC3/SPI2_MOSI/I2S2_SD/OTG_HS_ULPI_NXT/ETH_MII_TX_CLK/EVENTOUT/ADC123_IN13_11") (pintype "bidirectional"))
    )
    (net (code "27") (name "/US1_TRIG") (class "Default")
      (node (ref "P9") (pin "3") (pinfunction "3_3") (pintype "passive"))
      (node (ref "U1") (pin "10") (pinfunction "PC2/SPI2_MISO/OTG_HS_ULPI_DIR/ETH_MII_TXD2/I2S2ext_SD/EVENTOUT/ADC123_IN12_10") (pintype "bidirectional"))
    )
    (net (code "28") (name "/US2_ECHO") (class "Default")
      (node (ref "P10") (pin "2") (pinfunction "2_2") (pintype "passive"))
      (node (ref "U1") (pin "53") (pinfunction "PC12/UART5_TX/SDIO_CK/DCMI_D9/SPI3_MOSI/I2S3_SD/USART3_CK/EVENTOUT_53") (pintype "bidirectional"))
    )
    (net (code "29") (name "/US2_TRIG") (class "Default")
      (node (ref "P10") (pin "3") (pinfunction "3_3") (pintype "passive"))
      (node (ref "U1") (pin "52") (pinfunction "PC11/UART4_RX/SPI3_MISO/SDIO_D3/DCMI_D4/USART3_RX/I2S3ext_SD/EVENTOUT_52") (pintype "bidirectional"))
    )
    (net (code "30") (name "/US3_ECHO") (class "Default")
      (node (ref "P11") (pin "2") (pinfunction "2_2") (pintype "passive"))
      (node (ref "U1") (pin "39") (pinfunction "PC8/TIM8_CH3/SDIO_D0/TIM3_CH3/USART6_CK/DCMI_D2/EVENTOUT_39") (pintype "bidirectional"))
    )
    (net (code "31") (name "/US3_TRIG") (class "Default")
      (node (ref "P11") (pin "3") (pinfunction "3_3") (pintype "passive"))
      (node (ref "U1") (pin "38") (pinfunction "PC7/I2S3_MCK/TIM8_CH2/SDIO_D7/USART6_RX/DCMI_D1/TIM3_CH2/EVENTOUT_38") (pintype "bidirectional"))
    )
    (net (code "32") (name "/US4_ECHO") (class "Default")
      (node (ref "P12") (pin "2") (pinfunction "2_2") (pintype "passive"))
      (node (ref "U1") (pin "25") (pinfunction "PC5/ETH_RMII_RX_D1/ETH_MII_RX_D1/EVENTOUT/ADC12_IN15_25") (pintype "bidirectional"))
    )
    (net (code "33") (name "/US4_TRIG") (class "Default")
      (node (ref "P12") (pin "3") (pinfunction "3_3") (pintype "passive"))
      (node (ref "U1") (pin "24") (pinfunction "PC4/ETH_RMII_RX_D0/ETH_MII_RX_D0/EVENTOUT/ADC12_IN14_24") (pintype "bidirectional"))
    )
    (net (code "34") (name "/USB_CONN_N") (class "Default")
      (node (ref "D1") (pin "1") (pinfunction "I/O_1_1") (pintype "passive"))
      (node (ref "J1") (pin "2") (pinfunction "D-_2") (pintype "passive"))
    )
    (net (code "35") (name "/USB_CONN_P") (class "Default")
      (node (ref "D1") (pin "3") (pinfunction "I/O_2_3") (pintype "passive"))
      (node (ref "J1") (pin "3") (pinfunction "D+_3") (pintype "passive"))
    )
    (net (code "36") (name "/USB_N") (class "Default")
      (node (ref "D1") (pin "6") (pinfunction "I/O_4_6") (pintype "passive"))
      (node (ref "U1") (pin "44") (pinfunction "PA11/USART1_CTS/CAN1_RX/TIM1_CH4/OTG_FS_DM/EVENTOUT_44") (pintype "bidirectional"))
    )
    (net (code "37") (name "/USB_P") (class "Default")
      (node (ref "D1") (pin "4") (pinfunction "I/O_3_4") (pintype "passive"))
      (node (ref "U1") (pin "45") (pinfunction "PA12/USART1_RTS/CAN1_TX/TIM1_ETR/OTG_FS_DP/EVENTOUT_45") (pintype "bidirectional"))
    )
    (net (code "38") (name "3.3V") (class "Default")
      (node (ref "C10") (pin "2") (pinfunction "2_2") (pintype "passive"))
      (node (ref "C11") (pin "2") (pinfunction "2_2") (pintype "passive"))
      (node (ref "C12") (pin "2") (pinfunction "2_2") (pintype "passive"))
      (node (ref "C13") (pin "1") (pinfunction "1_1") (pintype "passive"))
      (node (ref "C16") (pin "1") (pinfunction "1_1") (pintype "passive"))
      (node (ref "C17") (pin "2") (pinfunction "2_2") (pintype "passive"))
      (node (ref "C18") (pin "2") (pinfunction "2_2") (pintype "passive"))
      (node (ref "C19") (pin "1") (pinfunction "1_1") (pintype "passive"))
      (node (ref "C20") (pin "1") (pinfunction "1_1") (pintype "passive"))
      (node (ref "C26") (pin "1") (pinfunction "1_1") (pintype "passive"))
      (node (ref "C5") (pin "2") (pinfunction "2_2") (pintype "passive"))
      (node (ref "C6") (pin "2") (pinfunction "2_2") (pintype "passive"))
      (node (ref "C7") (pin "2") (pinfunction "2_2") (pintype "passive"))
      (node (ref "C8") (pin "2") (pinfunction "2_2") (pintype "passive"))
      (node (ref "C9") (pin "2") (pinfunction "2_2") (pintype "passive"))
      (node (ref "L1") (pin "1") (pinfunction "1_1") (pintype "passive"))
      (node (ref "L2") (pin "1") (pinfunction "1_1") (pintype "passive"))
      (node (ref "MD1") (pin "6") (pinfunction "Vbatt_6") (pintype "input"))
      (node (ref "P2") (pin "4") (pinfunction "4_4") (pintype "passive"))
      (node (ref "P8") (pin "1") (pinfunction "1_1") (pintype "passive"))
      (node (ref "R1") (pin "2") (pinfunction "2_2") (pintype "passive"))
      (node (ref "R2") (pin "2") (pinfunction "2_2") (pintype "passive"))
      (node (ref "R3") (pin "2") (pinfunction "2_2") (pintype "passive"))
      (node (ref "R4") (pin "2") (pinfunction "2_2") (pintype "passive"))
      (node (ref "R9") (pin "1") (pinfunction "1_1") (pintype "passive"))
      (node (ref "U1") (pin "1") (pinfunction "VBAT_1") (pintype "power_in"))
      (node (ref "U1") (pin "13") (pinfunction "VDDA_13") (pintype "power_in"))
      (node (ref "U1") (pin "19") (pinfunction "VDD_19") (pintype "power_in"))
      (node (ref "U1") (pin "32") (pinfunction "VDD_32") (pintype "power_in"))
      (node (ref "U1") (pin "48") (pinfunction "VDD_48") (pintype "power_in"))
      (node (ref "U1") (pin "64") (pinfunction "VDD_64") (pintype "power_in"))
      (node (ref "U2") (pin "2") (pinfunction "VOUT_2") (pintype "passive"))
      (node (ref "U3") (pin "1") (pinfunction "RESV_1") (pintype "power_in"))
      (node (ref "U3") (pin "13") (pinfunction "VDD_13") (pintype "power_in"))
      (node (ref "U3") (pin "22") (pinfunction "nCS_22") (pintype "input"))
      (node (ref "U3") (pin "8") (pinfunction "VDDIO_8") (pintype "power_in"))
      (node (ref "U3") (pin "9") (pinfunction "AD0/SDO_9") (pintype "bidirectional"))
      (node (ref "U4") (pin "6") (pinfunction "VDDIO_6") (pintype "power_in"))
      (node (ref "U4") (pin "8") (pinfunction "VDD_8") (pintype "power_in"))
      (node (ref "U6") (pin "4") (pinfunction "VCC_4") (pintype "power_in"))
    )
    (net (code "39") (name "5V") (class "Default")
      (node (ref "C23") (pin "1") (pinfunction "1_1") (pintype "passive"))
      (node (ref "P10") (pin "4") (pinfunction "4_4") (pintype "passive"))
      (node (ref "P11") (pin "4") (pinfunction "4_4") (pintype "passive"))
      (node (ref "P12") (pin "4") (pinfunction "4_4") (pintype "passive"))
      (node (ref "P9") (pin "4") (pinfunction "4_4") (pintype "passive"))
      (node (ref "U5") (pin "2") (pinfunction "VOUT_2") (pintype "passive"))
    )
    (net (code "40") (name "GND") (class "Default")
      (node (ref "C1") (pin "2") (pinfunction "2_2") (pintype "passive"))
      (node (ref "C10") (pin "1") (pinfunction "1_1") (pintype "passive"))
      (node (ref "C11") (pin "1") (pinfunction "1_1") (pintype "passive"))
      (node (ref "C12") (pin "1") (pinfunction "1_1") (pintype "passive"))
      (node (ref "C13") (pin "2") (pinfunction "2_2") (pintype "passive"))
      (node (ref "C14") (pin "1") (pinfunction "1_1") (pintype "passive"))
      (node (ref "C15") (pin "2") (pinfunction "2_2") (pintype "passive"))
      (node (ref "C16") (pin "2") (pinfunction "2_2") (pintype "passive"))
      (node (ref "C17") (pin "1") (pinfunction "1_1") (pintype "passive"))
      (node (ref "C18") (pin "1") (pinfunction "1_1") (pintype "passive"))
      (node (ref "C19") (pin "2") (pinfunction "2_2") (pintype "passive"))
      (node (ref "C2") (pin "2") (pinfunction "2_2") (pintype "passive"))
      (node (ref "C20") (pin "2") (pinfunction "2_2") (pintype "passive"))
      (node (ref "C21") (pin "2") (pinfunction "2_2") (pintype "passive"))
      (node (ref "C22") (pin "2") (pinfunction "2_2") (pintype "passive"))
      (node (ref "C23") (pin "2") (pinfunction "2_2") (pintype "passive"))
      (node (ref "C24") (pin "1") (pinfunction "1_1") (pintype "passive"))
      (node (ref "C26") (pin "2") (pinfunction "2_2") (pintype "passive"))
      (node (ref "C3") (pin "1") (pinfunction "1_1") (pintype "passive"))
      (node (ref "C4") (pin "1") (pinfunction "1_1") (pintype "passive"))
      (node (ref "C5") (pin "1") (pinfunction "1_1") (pintype "passive"))
      (node (ref "C6") (pin "1") (pinfunction "1_1") (pintype "passive"))
      (node (ref "C7") (pin "1") (pinfunction "1_1") (pintype "passive"))
      (node (ref "C8") (pin "1") (pinfunction "1_1") (pintype "passive"))
      (node (ref "C9") (pin "1") (pinfunction "1_1") (pintype "passive"))
      (node (ref "D1") (pin "2") (pinfunction "GND_2") (pintype "passive"))
      (node (ref "D4") (pin "1") (pinfunction "C_1") (pintype "passive"))
      (node (ref "D5") (pin "1") (pinfunction "C_1") (pintype "passive"))
      (node (ref "J1") (pin "5") (pinfunction "GND_5") (pintype "power_in"))
      (node (ref "J2") (pin "2") (pinfunction "GND_2") (pintype "power_in"))
      (node (ref "J2") (pin "3") (pinfunction "GND_3") (pintype "power_in"))
      (node (ref "J2") (pin "4") (pinfunction "GND_4") (pintype "power_in"))
      (node (ref "J2") (pin "5") (pinfunction "GND_5") (pintype "power_in"))
      (node (ref "MD1") (pin "1") (pinfunction "GND_1") (pintype "power_in"))
      (node (ref "MD1") (pin "10") (pinfunction "GND_RF_10") (pintype "input"))
      (node (ref "MD1") (pin "12") (pinfunction "GND_RF_12") (pintype "input"))
      (node (ref "P10") (pin "1") (pinfunction "1_1") (pintype "passive"))
      (node (ref "P11") (pin "1") (pinfunction "1_1") (pintype "passive"))
      (node (ref "P12") (pin "1") (pinfunction "1_1") (pintype "passive"))
      (node (ref "P2") (pin "2") (pinfunction "2_2") (pintype "passive"))
      (node (ref "P3") (pin "1") (pinfunction "1_1") (pintype "passive"))
      (node (ref "P4") (pin "3") (pinfunction "3_3") (pintype "passive"))
      (node (ref "P5") (pin "3") (pinfunction "3_3") (pintype "passive"))
      (node (ref "P6") (pin "3") (pinfunction "3_3") (pintype "passive"))
      (node (ref "P7") (pin "3") (pinfunction "3_3") (pintype "passive"))
      (node (ref "P8") (pin "3") (pinfunction "3_3") (pintype "passive"))
      (node (ref "P9") (pin "1") (pinfunction "1_1") (pintype "passive"))
      (node (ref "R7") (pin "2") (pinfunction "2_2") (pintype "passive"))
      (node (ref "U1") (pin "12") (pinfunction "VSSA_12") (pintype "power_in"))
      (node (ref "U1") (pin "18") (pinfunction "VSS_18") (pintype "power_in"))
      (node (ref "U1") (pin "63") (pinfunction "VSS_63") (pintype "power_in"))
      (node (ref "U2") (pin "1") (pinfunction "Ground_1") (pintype "power_in"))
      (node (ref "U3") (pin "11") (pinfunction "FSYNC_11") (pintype "input"))
      (node (ref "U3") (pin "18") (pinfunction "GND_18") (pintype "power_in"))
      (node (ref "U3") (pin "20") (pinfunction "RESV_20") (pintype "power_in"))
      (node (ref "U4") (pin "1") (pinfunction "GND_1") (pintype "power_in"))
      (node (ref "U4") (pin "7") (pinfunction "GND_7") (pintype "power_in"))
      (node (ref "U5") (pin "1") (pinfunction "Ground_1") (pintype "power_in"))
      (node (ref "U6") (pin "1") (pinfunction "GND_1") (pintype "power_in"))
      (node (ref "U6") (pin "2") (pinfunction "GND_2") (pintype "power_in"))
      (node (ref "Y1") (pin "2") (pinfunction "GND_2") (pintype "power_in"))
      (node (ref "Y1") (pin "4") (pinfunction "GND_4") (pintype "power_in"))
    )
    (net (code "41") (name "Net-(C2-Pad1)") (class "Default")
      (node (ref "C2") (pin "1") (pinfunction "1_1") (pintype "passive"))
      (node (ref "R6") (pin "1") (pinfunction "1_1") (pintype "passive"))
      (node (ref "Y1") (pin "3") (pinfunction "3_3") (pintype "passive"))
    )
    (net (code "42") (name "Net-(C25-Pad2)") (class "Default")
      (node (ref "C25") (pin "2") (pinfunction "2_2") (pintype "passive"))
      (node (ref "L3") (pin "1") (pinfunction "1_1") (pintype "passive"))
    )
    (net (code "43") (name "Net-(D2-K)") (class "Default")
      (node (ref "D2") (pin "2") (pinfunction "K_2") (pintype "passive"))
      (node (ref "D3") (pin "2") (pinfunction "K_2") (pintype "passive"))
      (node (ref "F1") (pin "1") (pinfunction "1_1") (pintype "passive"))
    )
    (net (code "44") (name "Net-(D4-A)") (class "Default")
      (node (ref "D4") (pin "2") (pinfunction "A_2") (pintype "passive"))
      (node (ref "R8") (pin "1") (pinfunction "1_1") (pintype "passive"))
    )
    (net (code "45") (name "Net-(D5-A)") (class "Default")
      (node (ref "D5") (pin "2") (pinfunction "A_2") (pintype "passive"))
      (node (ref "R9") (pin "2") (pinfunction "2_2") (pintype "passive"))
    )
    (net (code "46") (name "Net-(F1-Pad2)") (class "Default")
      (node (ref "F1") (pin "2") (pinfunction "2_2") (pintype "passive"))
      (node (ref "FB1") (pin "1") (pinfunction "1_1") (pintype "passive"))
    )
    (net (code "47") (name "Net-(J2-Signal)") (class "Default")
      (node (ref "C25") (pin "1") (pinfunction "1_1") (pintype "passive"))
      (node (ref "J2") (pin "1") (pinfunction "Signal_1") (pintype "input"))
    )
    (net (code "48") (name "Net-(MD1-1PPS)") (class "Default")
      (node (ref "C21") (pin "1") (pinfunction "1_1") (pintype "passive"))
      (node (ref "MD1") (pin "4") (pinfunction "1PPS_4") (pintype "output"))
      (node (ref "R8") (pin "2") (pinfunction "2_2") (pintype "passive"))
    )
    (net (code "49") (name "Net-(P8-Pad2)") (class "Default")
      (node (ref "P8") (pin "2") (pinfunction "2_2") (pintype "passive"))
      (node (ref "R5") (pin "2") (pinfunction "2_2") (pintype "passive"))
    )
    (net (code "50") (name "Net-(U1C-VCAP_1)") (class "Default")
      (node (ref "C3") (pin "2") (pinfunction "2_2") (pintype "passive"))
      (node (ref "U1") (pin "31") (pinfunction "VCAP_1_31") (pintype "power_in"))
    )
    (net (code "51") (name "Net-(U1C-VCAP_2)") (class "Default")
      (node (ref "C4") (pin "2") (pinfunction "2_2") (pintype "passive"))
      (node (ref "U1") (pin "47") (pinfunction "VCAP_2_47") (pintype "power_in"))
    )
    (net (code "52") (name "Net-(U2-VIN)") (class "Default")
      (node (ref "C15") (pin "1") (pinfunction "1_1") (pintype "passive"))
      (node (ref "C22") (pin "1") (pinfunction "1_1") (pintype "passive"))
      (node (ref "FB1") (pin "2") (pinfunction "2_2") (pintype "passive"))
      (node (ref "U2") (pin "3") (pinfunction "VIN_3") (pintype "power_in"))
      (node (ref "U5") (pin "3") (pinfunction "VIN_3") (pintype "power_in"))
    )
    (net (code "53") (name "Net-(U3A-REGOUT)") (class "Default")
      (node (ref "C24") (pin "2") (pinfunction "2_2") (pintype "passive"))
      (node (ref "U3") (pin "10") (pinfunction "REGOUT_10") (pintype "passive"))
    )
    (net (code "54") (name "Net-(U6-RFIN)") (class "Default")
      (node (ref "L3") (pin "2") (pinfunction "2_2") (pintype "passive"))
      (node (ref "U6") (pin "3") (pinfunction "RFIN_3") (pintype "input"))
    )
    (net (code "55") (name "VBAT") (class "Default")
      (node (ref "D2") (pin "1") (pinfunction "A_1") (pintype "passive"))
      (node (ref "P3") (pin "2") (pinfunction "2_2") (pintype "passive"))
    )
    (net (code "56") (name "VUSB") (class "Default")
      (node (ref "D1") (pin "5") (pinfunction "VBUS_5") (pintype "passive"))
      (node (ref "D3") (pin "1") (pinfunction "A_1") (pintype "passive"))
      (node (ref "J1") (pin "1") (pinfunction "VBUS_1") (pintype "power_in"))
    )
    (net (code "57") (name "unconnected-(J1-ID-Pad4)") (class "Default")
      (node (ref "J1") (pin "4") (pinfunction "ID_4") (pintype "passive+no_connect"))
    )
    (net (code "58") (name "unconnected-(J1-SHLD1-Pad6)") (class "Default")
      (node (ref "J1") (pin "6") (pinfunction "SHLD1_6") (pintype "passive+no_connect"))
    )
    (net (code "59") (name "unconnected-(J1-SHLD2-Pad7)") (class "Default")
      (node (ref "J1") (pin "7") (pinfunction "SHLD2_7") (pintype "passive+no_connect"))
    )
    (net (code "60") (name "unconnected-(J1-SHLD3-Pad8)") (class "Default")
      (node (ref "J1") (pin "8") (pinfunction "SHLD3_8") (pintype "passive+no_connect"))
    )
    (net (code "61") (name "unconnected-(J1-SHLD4-Pad9)") (class "Default")
      (node (ref "J1") (pin "9") (pinfunction "SHLD4_9") (pintype "passive+no_connect"))
    )
    (net (code "62") (name "unconnected-(MD1-RESERVED-Pad15)") (class "Default")
      (node (ref "MD1") (pin "15") (pinfunction "RESERVED_15") (pintype "passive+no_connect"))
    )
    (net (code "63") (name "unconnected-(MD1-RESERVED-Pad18)") (class "Default")
      (node (ref "MD1") (pin "18") (pinfunction "RESERVED_18") (pintype "passive+no_connect"))
    )
    (net (code "64") (name "unconnected-(MD1-RX-Pad3)") (class "Default")
      (node (ref "MD1") (pin "3") (pinfunction "RX_3") (pintype "input+no_connect"))
    )
    (net (code "65") (name "unconnected-(MD1-TX-Pad2)") (class "Default")
      (node (ref "MD1") (pin "2") (pinfunction "TX_2") (pintype "output+no_connect"))
    )
    (net (code "66") (name "unconnected-(MD1-VCC_RF-Pad14)") (class "Default")
      (node (ref "MD1") (pin "14") (pinfunction "VCC_RF_14") (pintype "output+no_connect"))
    )
    (net (code "67") (name "unconnected-(P4-Pad2)") (class "Default")
      (node (ref "P4") (pin "2") (pinfunction "2_2") (pintype "passive+no_connect"))
    )
    (net (code "68") (name "unconnected-(P5-Pad2)") (class "Default")
      (node (ref "P5") (pin "2") (pinfunction "2_2") (pintype "passive+no_connect"))
    )
    (net (code "69") (name "unconnected-(P6-Pad2)") (class "Default")
      (node (ref "P6") (pin "2") (pinfunction "2_2") (pintype "passive+no_connect"))
    )
    (net (code "70") (name "unconnected-(P7-Pad2)") (class "Default")
      (node (ref "P7") (pin "2") (pinfunction "2_2") (pintype "passive+no_connect"))
    )
    (net (code "71") (name "unconnected-(U1A-PA0-WKUP(PA0){slash}USART2_CTS{slash}UART4_TX{slash}ETH_MII_CRS{slash}TIM2_CH1_ETR{slash}TIM5_CH1{slash}TIM8_ETR{slash}EVENTOUT{slash}ADC123_IN0{slash}WKUP-Pad14)") (class "Default")
      (node (ref "U1") (pin "14") (pinfunction "PA0-WKUP(PA0)/USART2_CTS/UART4_TX/ETH_MII_CRS/TIM2_CH1_ETR/TIM5_CH1/TIM8_ETR/EVENTOUT/ADC123_IN0/WKUP_14") (pintype "bidirectional+no_connect"))
    )
    (net (code "72") (name "unconnected-(U1A-PA1{slash}USART2_RTS{slash}UART4_RX{slash}ETH_RMII_REF_CLK{slash}ETH_MII_RX_CLK{slash}TIM5_CH2{slash}TIM2_CH2{slash}EVENTOUT{slash}ADC123_IN1-Pad15)") (class "Default")
      (node (ref "U1") (pin "15") (pinfunction "PA1/USART2_RTS/UART4_RX/ETH_RMII_REF_CLK/ETH_MII_RX_CLK/TIM5_CH2/TIM2_CH2/EVENTOUT/ADC123_IN1_15") (pintype "bidirectional+no_connect"))
    )
    (net (code "73") (name "unconnected-(U1A-PA3{slash}USART2_RX{slash}TIM5_CH4{slash}TIM9_CH2{slash}TIM2_CH4{slash}OTG_HS_ULPI_D0{slash}ETH_MII_COL{slash}EVENTOUT{slash}ADC123_IN3-Pad17)") (class "Default")
      (node (ref "U1") (pin "17") (pinfunction "PA3/USART2_RX/TIM5_CH4/TIM9_CH2/TIM2_CH4/OTG_HS_ULPI_D0/ETH_MII_COL/EVENTOUT/ADC123_IN3_17") (pintype "bidirectional+no_connect"))
    )
    (net (code "74") (name "unconnected-(U1A-PB0{slash}TIM3_CH3{slash}TIM8_CH2N{slash}OTG_HS_ULPI_D1{slash}ETH_MII_RXD2{slash}TIM1_CH2N{slash}EVENTOUT{slash}ADC12_IN8-Pad26)") (class "Default")
      (node (ref "U1") (pin "26") (pinfunction "PB0/TIM3_CH3/TIM8_CH2N/OTG_HS_ULPI_D1/ETH_MII_RXD2/TIM1_CH2N/EVENTOUT/ADC12_IN8_26") (pintype "bidirectional+no_connect"))
    )
    (net (code "75") (name "unconnected-(U1A-PB1{slash}TIM3_CH4{slash}TIM8_CH3N{slash}OTG_HS_ULPI_D2{slash}ETH_MII_RXD3{slash}TIM1_CH3N{slash}EVENTOUT{slash}ADC12_IN9-Pad27)") (class "Default")
      (node (ref "U1") (pin "27") (pinfunction "PB1/TIM3_CH4/TIM8_CH3N/OTG_HS_ULPI_D2/ETH_MII_RXD3/TIM1_CH3N/EVENTOUT/ADC12_IN9_27") (pintype "bidirectional+no_connect"))
    )
    (net (code "76") (name "unconnected-(U1A-PB2-BOOT1(PB2){slash}EVENTOUT-Pad28)") (class "Default")
      (node (ref "U1") (pin "28") (pinfunction "PB2-BOOT1(PB2)/EVENTOUT_28") (pintype "bidirectional+no_connect"))
    )
    (net (code "77") (name "unconnected-(U1A-PB3(JTDO{slash}TRACESWO){slash}JTDO{slash}TRACESWO{slash}SPI3_SCK{slash}I2S3_CK{slash}TIM2_CH2{slash}SPI1_SCK{slash}EVENTOUT-Pad55)") (class "Default")
      (node (ref "U1") (pin "55") (pinfunction "PB3(JTDO/TRACESWO)/JTDO/TRACESWO/SPI3_SCK/I2S3_CK/TIM2_CH2/SPI1_SCK/EVENTOUT_55") (pintype "bidirectional+no_connect"))
    )
    (net (code "78") (name "unconnected-(U1A-PB4(NJTRST){slash}NJTRST{slash}SPI3_MISO{slash}TIM3_CH1{slash}SPI1_MISO{slash}I2S3ext_SD{slash}EVENTOUT-Pad56)") (class "Default")
      (node (ref "U1") (pin "56") (pinfunction "PB4(NJTRST)/NJTRST/SPI3_MISO/TIM3_CH1/SPI1_MISO/I2S3ext_SD/EVENTOUT_56") (pintype "bidirectional+no_connect"))
    )
    (net (code "79") (name "unconnected-(U1A-PB5{slash}I2C1_SMBA{slash}CAN2_RX{slash}OTG_HS_ULPI_D7{slash}ETH_PPS_OUT{slash}TIM3_CH2{slash}SPI1_MOSI{slash}SPI3_MOSI{slash}DCMI_D10{slash}I2S3_SD{slash}EVENTOUT-Pad57)") (class "Default")
      (node (ref "U1") (pin "57") (pinfunction "PB5/I2C1_SMBA/CAN2_RX/OTG_HS_ULPI_D7/ETH_PPS_OUT/TIM3_CH2/SPI1_MOSI/SPI3_MOSI/DCMI_D10/I2S3_SD/EVENTOUT_57") (pintype "bidirectional+no_connect"))
    )
    (net (code "80") (name "unconnected-(U1A-PB8{slash}TIM4_CH3{slash}SDIO_D4{slash}TIM10_CH1{slash}DCMI_D6{slash}ETH_MII_TXD3{slash}I2C1_SCL{slash}CAN1_RX{slash}EVENTOUT-Pad61)") (class "Default")
      (node (ref "U1") (pin "61") (pinfunction "PB8/TIM4_CH3/SDIO_D4/TIM10_CH1/DCMI_D6/ETH_MII_TXD3/I2C1_SCL/CAN1_RX/EVENTOUT_61") (pintype "bidirectional+no_connect"))
    )
    (net (code "81") (name "unconnected-(U1A-PB12{slash}SPI2_NSS{slash}I2S2_WS{slash}I2C2_SMBA{slash}USART3_CK{slash}TIM1_BKIN{slash}CAN2_RX{slash}OTG_HS_ULPI_D5{slash}ETH_RMII_TXD0{slash}ETH_MII_TXD0{slash}OTG_HS_ID{slash}EVENTOUT-Pad33)") (class "Default")
      (node (ref "U1") (pin "33") (pinfunction "PB12/SPI2_NSS/I2S2_WS/I2C2_SMBA/USART3_CK/TIM1_BKIN/CAN2_RX/OTG_HS_ULPI_D5/ETH_RMII_TXD0/ETH_MII_TXD0/OTG_HS_ID/EVENTOUT_33") (pintype "bidirectional+no_connect"))
    )
    (net (code "82") (name "unconnected-(U1A-PB13{slash}SPI2_SCK{slash}I2S2_CK{slash}USART3_CTS{slash}TIM1_CH1N{slash}CAN2_TX{slash}OTG_HS_ULPI_D6{slash}ETH_RMII_TXD1{slash}ETH_MII_TXD1{slash}EVENTOUT{slash}OTG_HS_VBUS-Pad34)") (class "Default")
      (node (ref "U1") (pin "34") (pinfunction "PB13/SPI2_SCK/I2S2_CK/USART3_CTS/TIM1_CH1N/CAN2_TX/OTG_HS_ULPI_D6/ETH_RMII_TXD1/ETH_MII_TXD1/EVENTOUT/OTG_HS_VBUS_34") (pintype "bidirectional+no_connect"))
    )
    (net (code "83") (name "unconnected-(U1A-PB15{slash}SPI2_MOSI{slash}I2S2_SD{slash}TIM1_CH3N{slash}TIM8_CH3N{slash}TIM12_CH2{slash}OTG_HS_DP{slash}EVENTOUT{slash}RTC_REFIN-Pad36)") (class "Default")
      (node (ref "U1") (pin "36") (pinfunction "PB15/SPI2_MOSI/I2S2_SD/TIM1_CH3N/TIM8_CH3N/TIM12_CH2/OTG_HS_DP/EVENTOUT/RTC_REFIN_36") (pintype "bidirectional+no_connect"))
    )
    (net (code "84") (name "unconnected-(U1B-PC0{slash}OTG_HS_ULPI_STP{slash}EVENTOUT{slash}ADC123_IN10-Pad8)") (class "Default")
      (node (ref "U1") (pin "8") (pinfunction "PC0/OTG_HS_ULPI_STP/EVENTOUT/ADC123_IN10_8") (pintype "bidirectional+no_connect"))
    )
    (net (code "85") (name "unconnected-(U1B-PC1{slash}ETH_MDC{slash}EVENTOUT{slash}ADC123_IN11-Pad9)") (class "Default")
      (node (ref "U1") (pin "9") (pinfunction "PC1/ETH_MDC/EVENTOUT/ADC123_IN11_9") (pintype "bidirectional+no_connect"))
    )
    (net (code "86") (name "unconnected-(U1B-PC6{slash}I2S2_MCK{slash}TIM8_CH1{slash}SDIO_D6{slash}USART6_TX{slash}DCMI_D0{slash}TIM3_CH1{slash}EVENTOUT-Pad37)") (class "Default")
      (node (ref "U1") (pin "37") (pinfunction "PC6/I2S2_MCK/TIM8_CH1/SDIO_D6/USART6_TX/DCMI_D0/TIM3_CH1/EVENTOUT_37") (pintype "bidirectional+no_connect"))
    )
    (net (code "87") (name "unconnected-(U1B-PC10{slash}SPI3_SCK{slash}I2S3_CK{slash}UART4_TX{slash}SDIO_D2{slash}DCMI_D8{slash}USART3_TX{slash}EVENTOUT-Pad51)") (class "Default")
      (node (ref "U1") (pin "51") (pinfunction "PC10/SPI3_SCK/I2S3_CK/UART4_TX/SDIO_D2/DCMI_D8/USART3_TX/EVENTOUT_51") (pintype "bidirectional+no_connect"))
    )
    (net (code "88") (name "unconnected-(U1B-PC13{slash}EVENTOUT{slash}RTC_OUT,RTC_TAMP1,RTC_TS-Pad2)") (class "Default")
      (node (ref "U1") (pin "2") (pinfunction "PC13/EVENTOUT/RTC_OUT,RTC_TAMP1,RTC_TS_2") (pintype "bidirectional+no_connect"))
    )
    (net (code "89") (name "unconnected-(U1B-PC14-OSC32_IN(PC14){slash}EVENTOUT{slash}OSC32_IN-Pad3)") (class "Default")
      (node (ref "U1") (pin "3") (pinfunction "PC14-OSC32_IN(PC14)/EVENTOUT/OSC32_IN_3") (pintype "bidirectional+no_connect"))
    )
    (net (code "90") (name "unconnected-(U1B-PC15-OSC32_OUT(PC15){slash}EVENTOUT{slash}OSC32_OUT-Pad4)") (class "Default")
      (node (ref "U1") (pin "4") (pinfunction "PC15-OSC32_OUT(PC15)/EVENTOUT/OSC32_OUT_4") (pintype "bidirectional+no_connect"))
    )
    (net (code "91") (name "unconnected-(U1B-PD2{slash}TIM3_ETR{slash}UART5_RX{slash}SDIO_CMD{slash}DCMI_D11{slash}EVENTOUT-Pad54)") (class "Default")
      (node (ref "U1") (pin "54") (pinfunction "PD2/TIM3_ETR/UART5_RX/SDIO_CMD/DCMI_D11/EVENTOUT_54") (pintype "bidirectional+no_connect"))
    )
    (net (code "92") (name "unconnected-(U1C-NRST-Pad7)") (class "Default")
      (node (ref "U1") (pin "7") (pinfunction "NRST_7") (pintype "bidirectional+no_connect"))
    )
    (net (code "93") (name "unconnected-(U2-VOUT-Pad4)") (class "Default")
      (node (ref "U2") (pin "4") (pinfunction "VOUT_4") (pintype "passive+no_connect"))
    )
    (net (code "94") (name "unconnected-(U3A-AUX_CL-Pad7)") (class "Default")
      (node (ref "U3") (pin "7") (pinfunction "AUX_CL_7") (pintype "output+no_connect"))
    )
    (net (code "95") (name "unconnected-(U3A-AUX_DA-Pad21)") (class "Default")
      (node (ref "U3") (pin "21") (pinfunction "AUX_DA_21") (pintype "bidirectional+no_connect"))
    )
    (net (code "96") (name "unconnected-(U3A-EP-Pad25)") (class "Default")
      (node (ref "U3") (pin "25") (pinfunction "EP_25") (pintype "passive+no_connect"))
    )
    (net (code "97") (name "unconnected-(U3A-INT-Pad12)") (class "Default")
      (node (ref "U3") (pin "12") (pinfunction "INT_12") (pintype "tri_state+no_connect"))
    )
    (net (code "98") (name "unconnected-(U3A-RESV-Pad19)") (class "Default")
      (node (ref "U3") (pin "19") (pinfunction "RESV_19") (pintype "passive+no_connect"))
    )
    (net (code "99") (name "unconnected-(U3B-NC-Pad2)") (class "Default")
      (node (ref "U3") (pin "2") (pinfunction "NC_2") (pintype "passive+no_connect"))
    )
    (net (code "100") (name "unconnected-(U3B-NC-Pad3)") (class "Default")
      (node (ref "U3") (pin "3") (pinfunction "NC_3") (pintype "passive+no_connect"))
    )
    (net (code "101") (name "unconnected-(U3B-NC-Pad4)") (class "Default")
      (node (ref "U3") (pin "4") (pinfunction "NC_4") (pintype "passive+no_connect"))
    )
    (net (code "102") (name "unconnected-(U3B-NC-Pad5)") (class "Default")
      (node (ref "U3") (pin "5") (pinfunction "NC_5") (pintype "passive+no_connect"))
    )
    (net (code "103") (name "unconnected-(U3B-NC-Pad6)") (class "Default")
      (node (ref "U3") (pin "6") (pinfunction "NC_6") (pintype "passive+no_connect"))
    )
    (net (code "104") (name "unconnected-(U3B-NC-Pad14)") (class "Default")
      (node (ref "U3") (pin "14") (pinfunction "NC_14") (pintype "passive+no_connect"))
    )
    (net (code "105") (name "unconnected-(U3B-NC-Pad15)") (class "Default")
      (node (ref "U3") (pin "15") (pinfunction "NC_15") (pintype "passive+no_connect"))
    )
    (net (code "106") (name "unconnected-(U3B-NC-Pad16)") (class "Default")
      (node (ref "U3") (pin "16") (pinfunction "NC_16") (pintype "passive+no_connect"))
    )
    (net (code "107") (name "unconnected-(U3B-NC-Pad17)") (class "Default")
      (node (ref "U3") (pin "17") (pinfunction "NC_17") (pintype "passive+no_connect"))
    )
    (net (code "108") (name "unconnected-(U4-CSB-Pad2)") (class "Default")
      (node (ref "U4") (pin "2") (pinfunction "CSB_2") (pintype "input+no_connect"))
    )
    (net (code "109") (name "unconnected-(U4-SDO-Pad5)") (class "Default")
      (node (ref "U4") (pin "5") (pinfunction "SDO_5") (pintype "bidirectional+no_connect"))
    )
    (net (code "110") (name "unconnected-(U5-VOUT-Pad4)") (class "Default")
      (node (ref "U5") (pin "4") (pinfunction "VOUT_4") (pintype "passive+no_connect"))
    )
  )
)
